# IRReceiver.net
KiCad netlist of a schematic drawn in Altium Designer
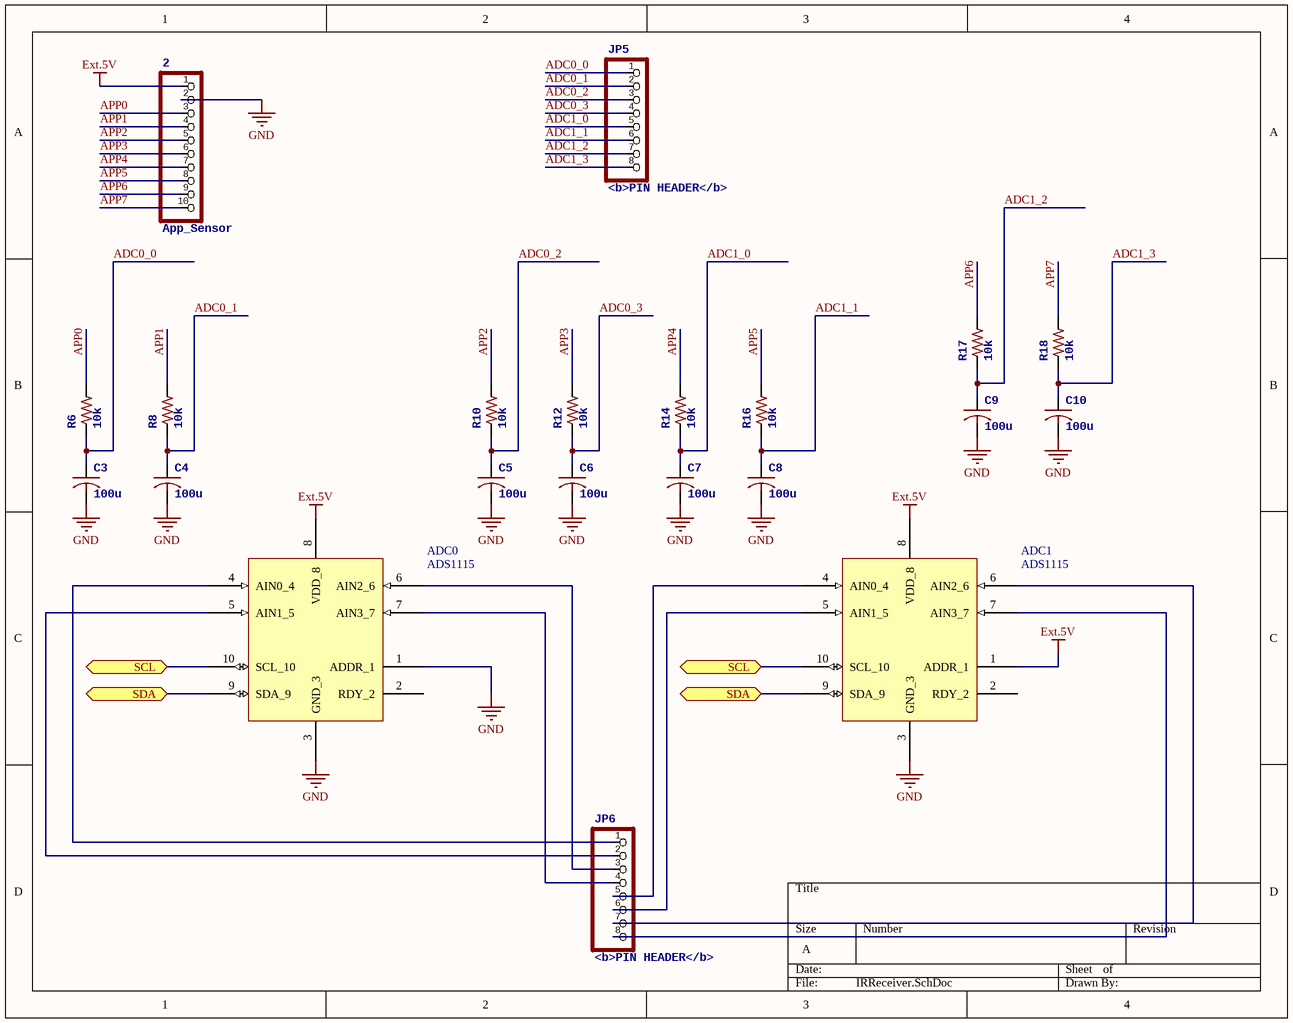
[diagram p0: IRReceiver.SchDoc]

(export (version "E")
  (design (tool "Eeschema 10.0.6"))
  (components
    (comp (ref "2")
      (value "App_Sensor")
      (footprint "1X10-BIG")
      (libsource (lib "adafruit") (part "PINHD-1X10"))
    )
    (comp (ref "ADC0") (value "ADS1115") (footprint "10-VSSOP") (libsource (lib "KLibrary") (part "ADS1115")))
    (comp (ref "ADC1") (value "ADS1115") (footprint "10-VSSOP") (libsource (lib "KLibrary") (part "ADS1115")))
    (comp (ref "C3") (value "100u") (footprint "C0805") (libsource (lib "adafruit") (part "C-USC0805")))
    (comp (ref "C4") (value "100u") (footprint "C0805") (libsource (lib "adafruit") (part "C-USC0805")))
    (comp (ref "C5") (value "100u") (footprint "C0805") (libsource (lib "adafruit") (part "C-USC0805")))
    (comp (ref "C6") (value "100u") (footprint "C0805") (libsource (lib "adafruit") (part "C-USC0805")))
    (comp (ref "C7") (value "100u") (footprint "C0805") (libsource (lib "adafruit") (part "C-USC0805")))
    (comp (ref "C8") (value "100u") (footprint "C0805") (libsource (lib "adafruit") (part "C-USC0805")))
    (comp (ref "C9") (value "100u") (footprint "C0805") (libsource (lib "adafruit") (part "C-USC0805")))
    (comp (ref "C10") (value "100u") (footprint "C0805") (libsource (lib "adafruit") (part "C-USC0805")))
    (comp (ref "JP5")
      (value "<b>PIN HEADER</b>")
      (footprint "1X08-BIG")
      (libsource (lib "adafruit") (part "PINHD-1X8BIG"))
    )
    (comp (ref "JP6")
      (value "<b>PIN HEADER</b>")
      (footprint "1X08-BIG")
      (libsource (lib "adafruit") (part "PINHD-1X8BIG"))
    )
    (comp (ref "R6") (value "10k") (footprint "R0805") (libsource (lib "adafruit") (part "R-US_R0805")))
    (comp (ref "R8") (value "10k") (footprint "R0805") (libsource (lib "adafruit") (part "R-US_R0805")))
    (comp (ref "R10") (value "10k") (footprint "R0805") (libsource (lib "adafruit") (part "R-US_R0805")))
    (comp (ref "R12") (value "10k") (footprint "R0805") (libsource (lib "adafruit") (part "R-US_R0805")))
    (comp (ref "R14") (value "10k") (footprint "R0805") (libsource (lib "adafruit") (part "R-US_R0805")))
    (comp (ref "R16") (value "10k") (footprint "R0805") (libsource (lib "adafruit") (part "R-US_R0805")))
    (comp (ref "R17") (value "10k") (footprint "R0805") (libsource (lib "adafruit") (part "R-US_R0805")))
    (comp (ref "R18") (value "10k") (footprint "R0805") (libsource (lib "adafruit") (part "R-US_R0805")))
  )
  (nets
    (net (code "1") (name "/ADC0_0") (class "Default")
      (node (ref "C3") (pin "1") (pinfunction "1_1") (pintype "passive"))
      (node (ref "JP5") (pin "1") (pinfunction "1_1") (pintype "passive"))
      (node (ref "R6") (pin "1") (pinfunction "1_1") (pintype "passive"))
    )
    (net (code "2") (name "/ADC0_1") (class "Default")
      (node (ref "C4") (pin "1") (pinfunction "1_1") (pintype "passive"))
      (node (ref "JP5") (pin "2") (pinfunction "2_2") (pintype "passive"))
      (node (ref "R8") (pin "1") (pinfunction "1_1") (pintype "passive"))
    )
    (net (code "3") (name "/ADC0_2") (class "Default")
      (node (ref "C5") (pin "1") (pinfunction "1_1") (pintype "passive"))
      (node (ref "JP5") (pin "3") (pinfunction "3_3") (pintype "passive"))
      (node (ref "R10") (pin "1") (pinfunction "1_1") (pintype "passive"))
    )
    (net (code "4") (name "/ADC0_3") (class "Default")
      (node (ref "C6") (pin "1") (pinfunction "1_1") (pintype "passive"))
      (node (ref "JP5") (pin "4") (pinfunction "4_4") (pintype "passive"))
      (node (ref "R12") (pin "1") (pinfunction "1_1") (pintype "passive"))
    )
    (net (code "5") (name "/ADC1_0") (class "Default")
      (node (ref "C7") (pin "1") (pinfunction "1_1") (pintype "passive"))
      (node (ref "JP5") (pin "5") (pinfunction "5_5") (pintype "passive"))
      (node (ref "R14") (pin "1") (pinfunction "1_1") (pintype "passive"))
    )
    (net (code "6") (name "/ADC1_1") (class "Default")
      (node (ref "C8") (pin "1") (pinfunction "1_1") (pintype "passive"))
      (node (ref "JP5") (pin "6") (pinfunction "6_6") (pintype "passive"))
      (node (ref "R16") (pin "1") (pinfunction "1_1") (pintype "passive"))
    )
    (net (code "7") (name "/ADC1_2") (class "Default")
      (node (ref "C9") (pin "1") (pinfunction "1_1") (pintype "passive"))
      (node (ref "JP5") (pin "7") (pinfunction "7_7") (pintype "passive"))
      (node (ref "R17") (pin "1") (pinfunction "1_1") (pintype "passive"))
    )
    (net (code "8") (name "/ADC1_3") (class "Default")
      (node (ref "C10") (pin "1") (pinfunction "1_1") (pintype "passive"))
      (node (ref "JP5") (pin "8") (pinfunction "8_8") (pintype "passive"))
      (node (ref "R18") (pin "1") (pinfunction "1_1") (pintype "passive"))
    )
    (net (code "9") (name "/APP0") (class "Default")
      (node (ref "2") (pin "3") (pinfunction "3_3") (pintype "passive"))
      (node (ref "R6") (pin "2") (pinfunction "2_2") (pintype "passive"))
    )
    (net (code "10") (name "/APP1") (class "Default")
      (node (ref "2") (pin "4") (pinfunction "4_4") (pintype "passive"))
      (node (ref "R8") (pin "2") (pinfunction "2_2") (pintype "passive"))
    )
    (net (code "11") (name "/APP2") (class "Default")
      (node (ref "2") (pin "5") (pinfunction "5_5") (pintype "passive"))
      (node (ref "R10") (pin "2") (pinfunction "2_2") (pintype "passive"))
    )
    (net (code "12") (name "/APP3") (class "Default")
      (node (ref "2") (pin "6") (pinfunction "6_6") (pintype "passive"))
      (node (ref "R12") (pin "2") (pinfunction "2_2") (pintype "passive"))
    )
    (net (code "13") (name "/APP4") (class "Default")
      (node (ref "2") (pin "7") (pinfunction "7_7") (pintype "passive"))
      (node (ref "R14") (pin "2") (pinfunction "2_2") (pintype "passive"))
    )
    (net (code "14") (name "/APP5") (class "Default")
      (node (ref "2") (pin "8") (pinfunction "8_8") (pintype "passive"))
      (node (ref "R16") (pin "2") (pinfunction "2_2") (pintype "passive"))
    )
    (net (code "15") (name "/APP6") (class "Default")
      (node (ref "2") (pin "9") (pinfunction "9_9") (pintype "passive"))
      (node (ref "R17") (pin "2") (pinfunction "2_2") (pintype "passive"))
    )
    (net (code "16") (name "/APP7") (class "Default")
      (node (ref "2") (pin "10") (pinfunction "10_10") (pintype "passive"))
      (node (ref "R18") (pin "2") (pinfunction "2_2") (pintype "passive"))
    )
    (net (code "17") (name "/SCL") (class "Default")
      (node (ref "ADC0") (pin "10") (pinfunction "SCL_10_10") (pintype "bidirectional"))
      (node (ref "ADC1") (pin "10") (pinfunction "SCL_10_10") (pintype "bidirectional"))
    )
    (net (code "18") (name "/SDA") (class "Default")
      (node (ref "ADC0") (pin "9") (pinfunction "SDA_9_9") (pintype "bidirectional"))
      (node (ref "ADC1") (pin "9") (pinfunction "SDA_9_9") (pintype "bidirectional"))
    )
    (net (code "19") (name "Ext.5V") (class "Default")
      (node (ref "2") (pin "1") (pinfunction "1_1") (pintype "passive"))
      (node (ref "ADC0") (pin "8") (pinfunction "VDD_8_8") (pintype "power_in"))
      (node (ref "ADC1") (pin "1") (pinfunction "ADDR_1_1") (pintype "passive"))
      (node (ref "ADC1") (pin "8") (pinfunction "VDD_8_8") (pintype "power_in"))
    )
    (net (code "20") (name "GND") (class "Default")
      (node (ref "2") (pin "2") (pinfunction "2_2") (pintype "passive"))
      (node (ref "ADC0") (pin "1") (pinfunction "ADDR_1_1") (pintype "passive"))
      (node (ref "ADC0") (pin "3") (pinfunction "GND_3_3") (pintype "power_in"))
      (node (ref "ADC1") (pin "3") (pinfunction "GND_3_3") (pintype "power_in"))
      (node (ref "C10") (pin "2") (pinfunction "2_2") (pintype "passive"))
      (node (ref "C3") (pin "2") (pinfunction "2_2") (pintype "passive"))
      (node (ref "C4") (pin "2") (pinfunction "2_2") (pintype "passive"))
      (node (ref "C5") (pin "2") (pinfunction "2_2") (pintype "passive"))
      (node (ref "C6") (pin "2") (pinfunction "2_2") (pintype "passive"))
      (node (ref "C7") (pin "2") (pinfunction "2_2") (pintype "passive"))
      (node (ref "C8") (pin "2") (pinfunction "2_2") (pintype "passive"))
      (node (ref "C9") (pin "2") (pinfunction "2_2") (pintype "passive"))
    )
    (net (code "21") (name "Net-(ADC0-AIN0_4)") (class "Default")
      (node (ref "ADC0") (pin "4") (pinfunction "AIN0_4_4") (pintype "input"))
      (node (ref "JP6") (pin "1") (pinfunction "1_1") (pintype "passive"))
    )
    (net (code "22") (name "Net-(ADC0-AIN1_5)") (class "Default")
      (node (ref "ADC0") (pin "5") (pinfunction "AIN1_5_5") (pintype "input"))
      (node (ref "JP6") (pin "2") (pinfunction "2_2") (pintype "passive"))
    )
    (net (code "23") (name "Net-(ADC0-AIN2_6)") (class "Default")
      (node (ref "ADC0") (pin "6") (pinfunction "AIN2_6_6") (pintype "input"))
      (node (ref "JP6") (pin "3") (pinfunction "3_3") (pintype "passive"))
    )
    (net (code "24") (name "Net-(ADC0-AIN3_7)") (class "Default")
      (node (ref "ADC0") (pin "7") (pinfunction "AIN3_7_7") (pintype "input"))
      (node (ref "JP6") (pin "4") (pinfunction "4_4") (pintype "passive"))
    )
    (net (code "25") (name "Net-(ADC1-AIN0_4)") (class "Default")
      (node (ref "ADC1") (pin "4") (pinfunction "AIN0_4_4") (pintype "input"))
      (node (ref "JP6") (pin "5") (pinfunction "5_5") (pintype "passive"))
    )
    (net (code "26") (name "Net-(ADC1-AIN1_5)") (class "Default")
      (node (ref "ADC1") (pin "5") (pinfunction "AIN1_5_5") (pintype "input"))
      (node (ref "JP6") (pin "6") (pinfunction "6_6") (pintype "passive"))
    )
    (net (code "27") (name "Net-(ADC1-AIN2_6)") (class "Default")
      (node (ref "ADC1") (pin "6") (pinfunction "AIN2_6_6") (pintype "input"))
      (node (ref "JP6") (pin "7") (pinfunction "7_7") (pintype "passive"))
    )
    (net (code "28") (name "Net-(ADC1-AIN3_7)") (class "Default")
      (node (ref "ADC1") (pin "7") (pinfunction "AIN3_7_7") (pintype "input"))
      (node (ref "JP6") (pin "8") (pinfunction "8_8") (pintype "passive"))
    )
    (net (code "29") (name "unconnected-(ADC0-RDY_2-Pad2)") (class "Default")
      (node (ref "ADC0") (pin "2") (pinfunction "RDY_2_2") (pintype "passive"))
    )
    (net (code "30") (name "unconnected-(ADC1-RDY_2-Pad2)") (class "Default")
      (node (ref "ADC1") (pin "2") (pinfunction "RDY_2_2") (pintype "passive"))
    )
  )
)
